# Retr3dRTMini.net
KiCad netlist of a schematic drawn in EAGLE
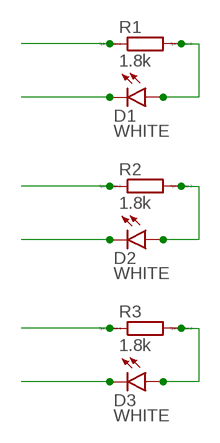
[diagram p0: schematic, sheet 1]

(export (version "E")
  (design (tool "Eeschema 10.0.6"))
  (components
    (comp (ref "D1")
      (value "WHITE")
      (footprint "eagle-import:LED-1206")
      (libsource (lib "eagle-import") (part "LED-WHITE1206"))
    )
    (comp (ref "D2")
      (value "WHITE")
      (footprint "eagle-import:LED-1206")
      (libsource (lib "eagle-import") (part "LED-WHITE1206"))
    )
    (comp (ref "D3")
      (value "WHITE")
      (footprint "eagle-import:LED-1206")
      (libsource (lib "eagle-import") (part "LED-WHITE1206"))
    )
    (comp (ref "R1")
      (value "1.8k")
      (footprint "eagle-import:R0805")
      (libsource (lib "eagle-import") (part "R"))
    )
    (comp (ref "R2")
      (value "1.8k")
      (footprint "eagle-import:R0805")
      (libsource (lib "eagle-import") (part "R"))
    )
    (comp (ref "R3")
      (value "1.8k")
      (footprint "eagle-import:R0805")
      (libsource (lib "eagle-import") (part "R"))
    )
  )
  (nets
    (net (code "1") (name "Net-(D1-PadA)") (class "Default")
      (node (ref "D1") (pin "A") (pinfunction "A_A") (pintype "passive"))
      (node (ref "R1") (pin "2") (pinfunction "2_2") (pintype "passive"))
    )
    (net (code "2") (name "Net-(D2-PadA)") (class "Default")
      (node (ref "D2") (pin "A") (pinfunction "A_A") (pintype "passive"))
      (node (ref "R2") (pin "2") (pinfunction "2_2") (pintype "passive"))
    )
    (net (code "3") (name "Net-(D3-PadA)") (class "Default")
      (node (ref "D3") (pin "A") (pinfunction "A_A") (pintype "passive"))
      (node (ref "R3") (pin "2") (pinfunction "2_2") (pintype "passive"))
    )
    (net (code "4") (name "unconnected-(D1-PadC)") (class "Default")
      (node (ref "D1") (pin "C") (pinfunction "C_C") (pintype "passive"))
    )
    (net (code "5") (name "unconnected-(D2-PadC)") (class "Default")
      (node (ref "D2") (pin "C") (pinfunction "C_C") (pintype "passive"))
    )
    (net (code "6") (name "unconnected-(D3-PadC)") (class "Default")
      (node (ref "D3") (pin "C") (pinfunction "C_C") (pintype "passive"))
    )
    (net (code "7") (name "unconnected-(R1-Pad1)") (class "Default")
      (node (ref "R1") (pin "1") (pinfunction "1_1") (pintype "passive"))
    )
    (net (code "8") (name "unconnected-(R2-Pad1)") (class "Default")
      (node (ref "R2") (pin "1") (pinfunction "1_1") (pintype "passive"))
    )
    (net (code "9") (name "unconnected-(R3-Pad1)") (class "Default")
      (node (ref "R3") (pin "1") (pinfunction "1_1") (pintype "passive"))
    )
  )
)
